# usb2rs232_v2_3.net
KiCad netlist of a schematic drawn in EAGLE
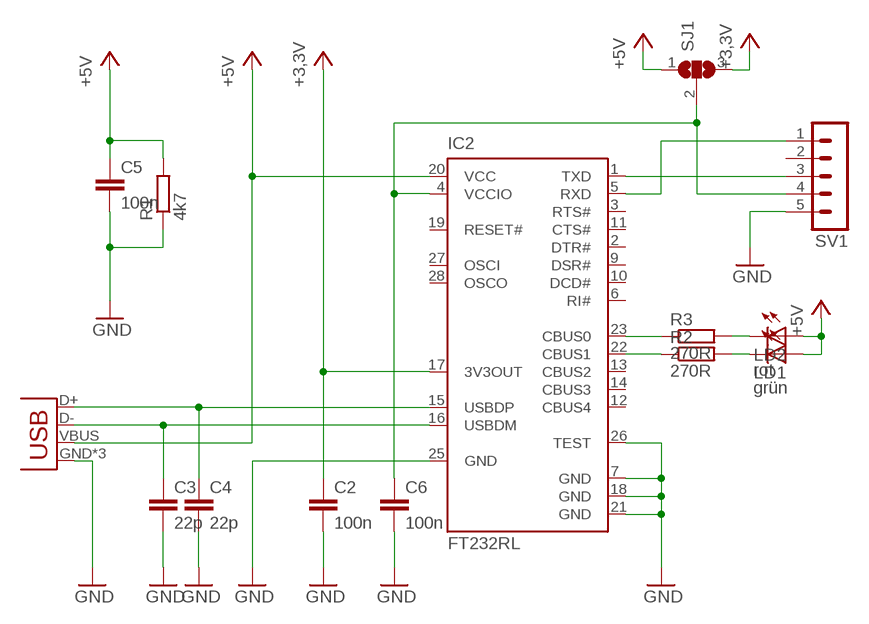
[diagram p0: schematic, sheet 1]

(export (version "E")
  (design (tool "Eeschema 10.0.6"))
  (components
    (comp (ref "C2")
      (value "100n")
      (footprint "eagle-import:C0603")
      (libsource (lib "eagle-import") (part "C-EUC0603"))
    )
    (comp (ref "C3")
      (value "22p")
      (footprint "eagle-import:C0603")
      (libsource (lib "eagle-import") (part "C-EUC0603"))
    )
    (comp (ref "C4")
      (value "22p")
      (footprint "eagle-import:C0603")
      (libsource (lib "eagle-import") (part "C-EUC0603"))
    )
    (comp (ref "C5")
      (value "100n")
      (footprint "eagle-import:C0603")
      (libsource (lib "eagle-import") (part "C-EUC0603"))
    )
    (comp (ref "C6")
      (value "100n")
      (footprint "eagle-import:C0603")
      (libsource (lib "eagle-import") (part "C-EUC0603"))
    )
    (comp (ref "IC2")
      (value "FT232RL")
      (footprint "eagle-import:SSOP28")
      (libsource (lib "eagle-import") (part "FT232RL"))
    )
    (comp (ref "JP2")
      (value "USB-MICROB")
      (footprint "eagle-import:USB-MICROB")
      (libsource (lib "eagle-import") (part "USB-MICROB"))
    )
    (comp (ref "LD1")
      (value "grün")
      (footprint "eagle-import:CHIP-LED0603")
      (libsource (lib "eagle-import") (part "LEDCHIP-LED0603"))
    )
    (comp (ref "LD2")
      (value "rot")
      (footprint "eagle-import:CHIP-LED0603")
      (libsource (lib "eagle-import") (part "LEDCHIP-LED0603"))
    )
    (comp (ref "R1")
      (value "4k7")
      (footprint "eagle-import:R0603")
      (libsource (lib "eagle-import") (part "R-EU_R0603"))
    )
    (comp (ref "R2")
      (value "270R")
      (footprint "eagle-import:R0603")
      (libsource (lib "eagle-import") (part "R-EU_R0603"))
    )
    (comp (ref "R3")
      (value "270R")
      (footprint "eagle-import:R0603")
      (libsource (lib "eagle-import") (part "R-EU_R0603"))
    )
    (comp (ref "SJ1")
      (value "SJ2W")
      (footprint "eagle-import:SJ_2")
      (libsource (lib "eagle-import") (part "SJ2W"))
    )
    (comp (ref "SV1")
      (value "MA05-1")
      (footprint "eagle-import:MA05-1")
      (libsource (lib "eagle-import") (part "MA05-1"))
    )
  )
  (nets
    (net (code "1") (name "+3,3V") (class "Default")
      (node (ref "C2") (pin "1") (pinfunction "1_1") (pintype "passive"))
      (node (ref "IC2") (pin "17") (pinfunction "3V3OUT_17") (pintype "input"))
      (node (ref "SJ1") (pin "3") (pinfunction "3_3") (pintype "passive"))
    )
    (net (code "2") (name "+5V") (class "Default")
      (node (ref "C5") (pin "1") (pinfunction "1_1") (pintype "passive"))
      (node (ref "IC2") (pin "20") (pinfunction "VCC_20") (pintype "input"))
      (node (ref "JP2") (pin "VBUS") (pinfunction "VBUS_VBUS") (pintype "bidirectional"))
      (node (ref "LD1") (pin "A") (pinfunction "A_A") (pintype "passive"))
      (node (ref "LD2") (pin "A") (pinfunction "A_A") (pintype "passive"))
      (node (ref "R1") (pin "2") (pinfunction "2_2") (pintype "passive"))
      (node (ref "SJ1") (pin "1") (pinfunction "1_1") (pintype "passive"))
    )
    (net (code "3") (name "GND") (class "Default")
      (node (ref "C2") (pin "2") (pinfunction "2_2") (pintype "passive"))
      (node (ref "C3") (pin "2") (pinfunction "2_2") (pintype "passive"))
      (node (ref "C4") (pin "2") (pinfunction "2_2") (pintype "passive"))
      (node (ref "C5") (pin "2") (pinfunction "2_2") (pintype "passive"))
      (node (ref "C6") (pin "2") (pinfunction "2_2") (pintype "passive"))
      (node (ref "IC2") (pin "18") (pinfunction "GND_18") (pintype "input"))
      (node (ref "IC2") (pin "21") (pinfunction "GND_21") (pintype "input"))
      (node (ref "IC2") (pin "25") (pinfunction "GND_25") (pintype "input"))
      (node (ref "IC2") (pin "26") (pinfunction "TEST_26") (pintype "input"))
      (node (ref "IC2") (pin "7") (pinfunction "GND_7") (pintype "input"))
      (node (ref "JP2") (pin "GND") (pinfunction "GND_GND") (pintype "bidirectional"))
      (node (ref "JP2") (pin "MT1") (pinfunction "GND_MT1") (pintype "bidirectional"))
      (node (ref "JP2") (pin "MT2") (pinfunction "GND_MT2") (pintype "bidirectional"))
      (node (ref "R1") (pin "1") (pinfunction "1_1") (pintype "passive"))
      (node (ref "SV1") (pin "5") (pinfunction "5_5") (pintype "passive"))
    )
    (net (code "4") (name "Net-(IC2-CBUS0)") (class "Default")
      (node (ref "IC2") (pin "23") (pinfunction "CBUS0_23") (pintype "input"))
      (node (ref "R3") (pin "1") (pinfunction "1_1") (pintype "passive"))
    )
    (net (code "5") (name "Net-(IC2-CBUS1)") (class "Default")
      (node (ref "IC2") (pin "22") (pinfunction "CBUS1_22") (pintype "input"))
      (node (ref "R2") (pin "1") (pinfunction "1_1") (pintype "passive"))
    )
    (net (code "6") (name "Net-(IC2-RXD)") (class "Default")
      (node (ref "IC2") (pin "5") (pinfunction "RXD_5") (pintype "input"))
      (node (ref "SV1") (pin "1") (pinfunction "1_1") (pintype "passive"))
    )
    (net (code "7") (name "Net-(IC2-TXD)") (class "Default")
      (node (ref "IC2") (pin "1") (pinfunction "TXD_1") (pintype "input"))
      (node (ref "SV1") (pin "3") (pinfunction "3_3") (pintype "passive"))
    )
    (net (code "8") (name "Net-(IC2-USBDM)") (class "Default")
      (node (ref "C3") (pin "1") (pinfunction "1_1") (pintype "passive"))
      (node (ref "IC2") (pin "16") (pinfunction "USBDM_16") (pintype "input"))
      (node (ref "JP2") (pin "D-") (pinfunction "D-_D-") (pintype "bidirectional"))
    )
    (net (code "9") (name "Net-(IC2-USBDP)") (class "Default")
      (node (ref "C4") (pin "1") (pinfunction "1_1") (pintype "passive"))
      (node (ref "IC2") (pin "15") (pinfunction "USBDP_15") (pintype "input"))
      (node (ref "JP2") (pin "D+") (pinfunction "D+_D+") (pintype "bidirectional"))
    )
    (net (code "10") (name "Net-(IC2-VCCIO)") (class "Default")
      (node (ref "C6") (pin "1") (pinfunction "1_1") (pintype "passive"))
      (node (ref "IC2") (pin "4") (pinfunction "VCCIO_4") (pintype "input"))
      (node (ref "SJ1") (pin "2") (pinfunction "2_2") (pintype "passive"))
      (node (ref "SV1") (pin "4") (pinfunction "4_4") (pintype "passive"))
    )
    (net (code "11") (name "Net-(LD1-PadC)") (class "Default")
      (node (ref "LD1") (pin "C") (pinfunction "C_C") (pintype "passive"))
      (node (ref "R2") (pin "2") (pinfunction "2_2") (pintype "passive"))
    )
    (net (code "12") (name "Net-(LD2-PadC)") (class "Default")
      (node (ref "LD2") (pin "C") (pinfunction "C_C") (pintype "passive"))
      (node (ref "R3") (pin "2") (pinfunction "2_2") (pintype "passive"))
    )
    (net (code "13") (name "unconnected-(IC2-CBUS2-Pad13)") (class "Default")
      (node (ref "IC2") (pin "13") (pinfunction "CBUS2_13") (pintype "input"))
    )
    (net (code "14") (name "unconnected-(IC2-CBUS3-Pad14)") (class "Default")
      (node (ref "IC2") (pin "14") (pinfunction "CBUS3_14") (pintype "input"))
    )
    (net (code "15") (name "unconnected-(IC2-CBUS4-Pad12)") (class "Default")
      (node (ref "IC2") (pin "12") (pinfunction "CBUS4_12") (pintype "input"))
    )
    (net (code "16") (name "unconnected-(IC2-CTS#-Pad11)") (class "Default")
      (node (ref "IC2") (pin "11") (pinfunction "CTS#_11") (pintype "input"))
    )
    (net (code "17") (name "unconnected-(IC2-DCD#-Pad10)") (class "Default")
      (node (ref "IC2") (pin "10") (pinfunction "DCD#_10") (pintype "input"))
    )
    (net (code "18") (name "unconnected-(IC2-DSR#-Pad9)") (class "Default")
      (node (ref "IC2") (pin "9") (pinfunction "DSR#_9") (pintype "input"))
    )
    (net (code "19") (name "unconnected-(IC2-DTR#-Pad2)") (class "Default")
      (node (ref "IC2") (pin "2") (pinfunction "DTR#_2") (pintype "input"))
    )
    (net (code "20") (name "unconnected-(IC2-OSCI-Pad27)") (class "Default")
      (node (ref "IC2") (pin "27") (pinfunction "OSCI_27") (pintype "input"))
    )
    (net (code "21") (name "unconnected-(IC2-OSCO-Pad28)") (class "Default")
      (node (ref "IC2") (pin "28") (pinfunction "OSCO_28") (pintype "input"))
    )
    (net (code "22") (name "unconnected-(IC2-RESET#-Pad19)") (class "Default")
      (node (ref "IC2") (pin "19") (pinfunction "RESET#_19") (pintype "input"))
    )
    (net (code "23") (name "unconnected-(IC2-RI#-Pad6)") (class "Default")
      (node (ref "IC2") (pin "6") (pinfunction "RI#_6") (pintype "input"))
    )
    (net (code "24") (name "unconnected-(IC2-RTS#-Pad3)") (class "Default")
      (node (ref "IC2") (pin "3") (pinfunction "RTS#_3") (pintype "input"))
    )
    (net (code "25") (name "unconnected-(SV1-Pad2)") (class "Default")
      (node (ref "SV1") (pin "2") (pinfunction "2_2") (pintype "passive"))
    )
  )
)
